# Babel_Wing_Rev_A.net
KiCad netlist of a schematic drawn in EAGLE
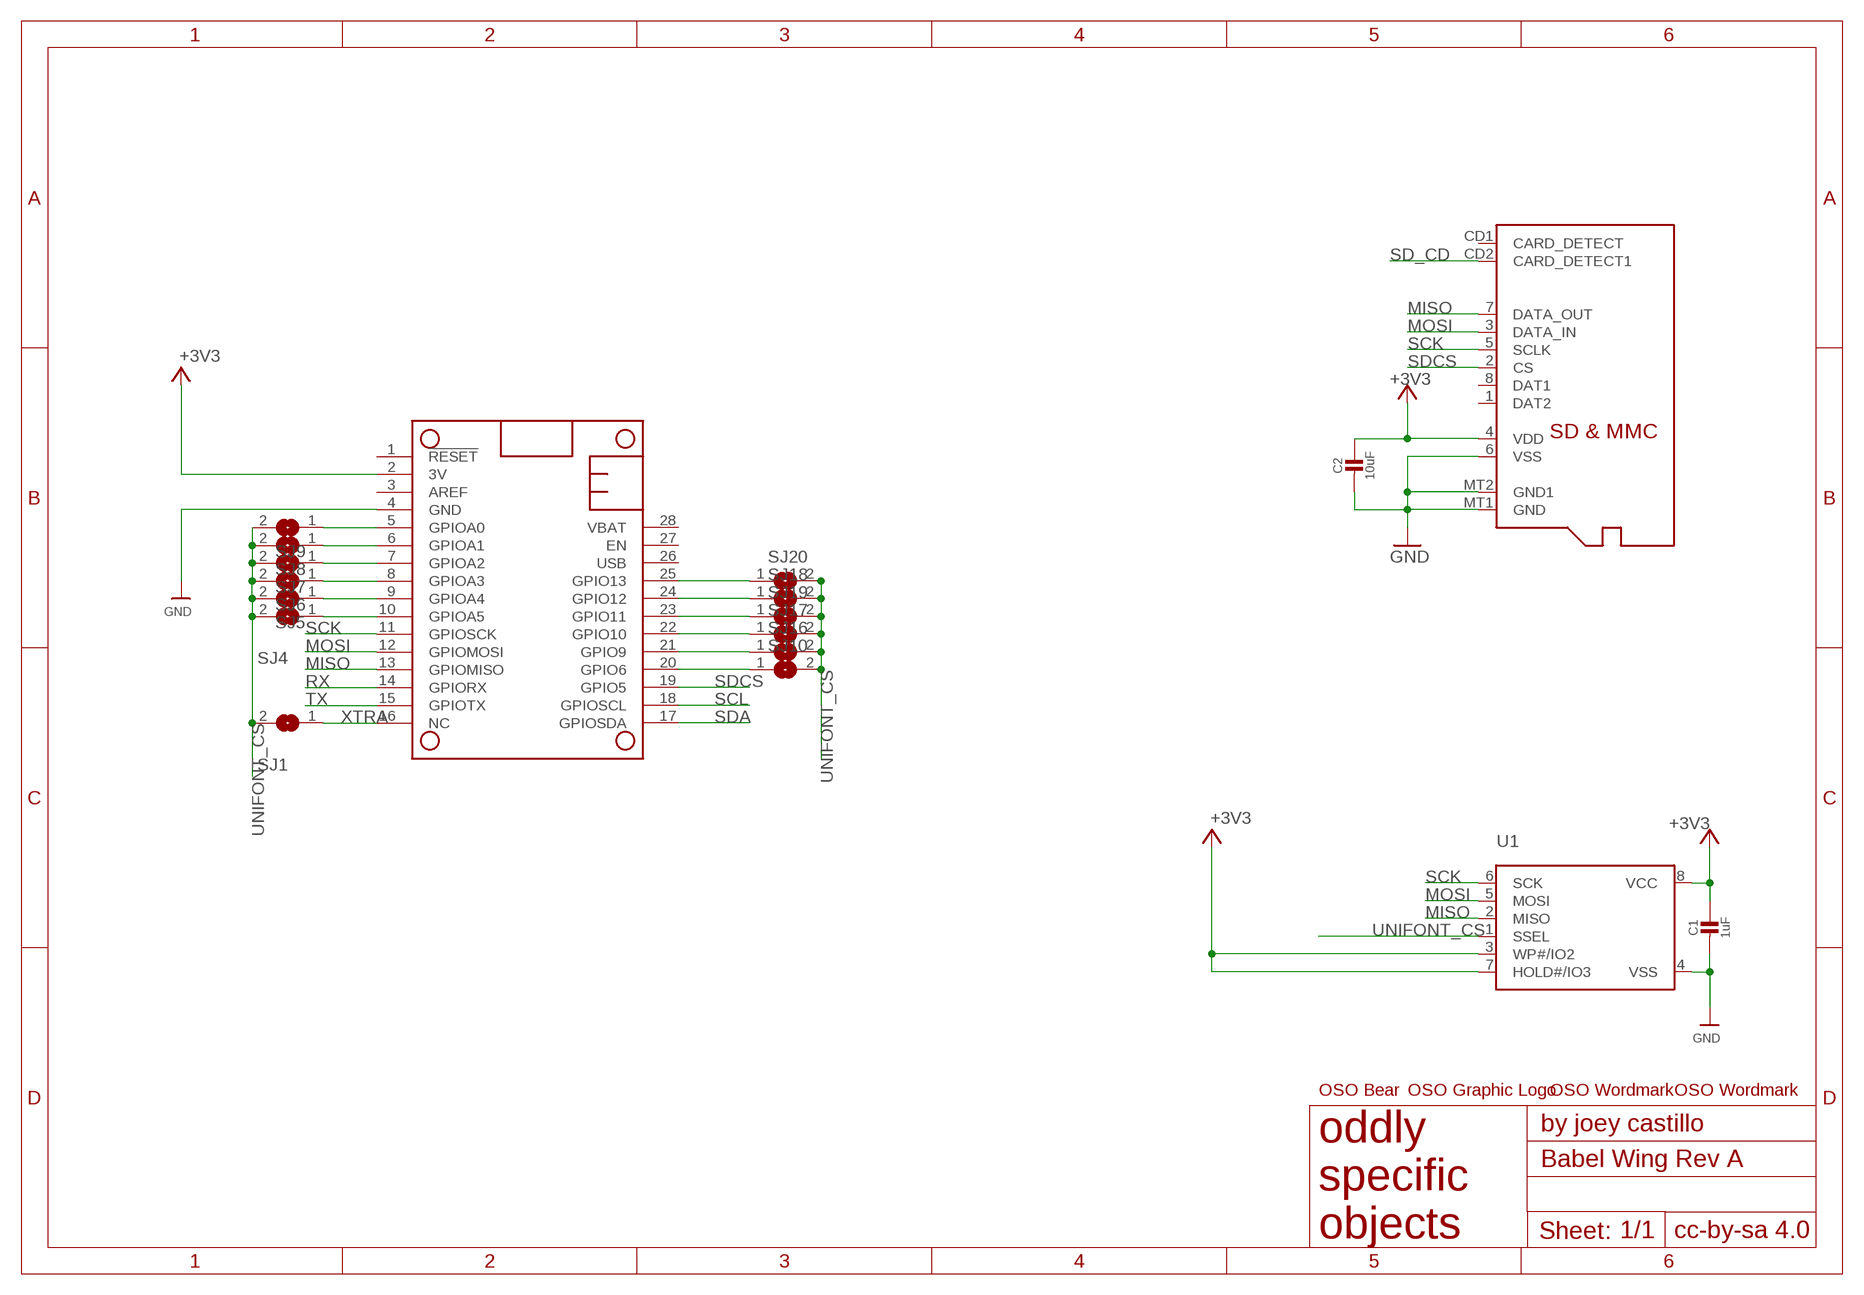
[diagram p0: schematic, sheet 1]

(export (version "E")
  (design (tool "Eeschema 10.0.6"))
  (components
    (comp (ref "C1")
      (value "1uF")
      (footprint "eagle-import:0805_10MGAP")
      (libsource (lib "eagle-import") (part "CAP_CERAMIC0805_10MGAP"))
    )
    (comp (ref "C2")
      (value "10uF")
      (footprint "eagle-import:0805_10MGAP")
      (libsource (lib "eagle-import") (part "CAP_CERAMIC0805_10MGAP"))
    )
    (comp (ref "MICROSD")
      (value "MICROSD")
      (footprint "eagle-import:MICROSD")
      (libsource (lib "eagle-import") (part "MICROSD"))
    )
    (comp (ref "MS1")
      (value "FEATHERWING")
      (footprint "eagle-import:FEATHERWING")
      (libsource (lib "eagle-import") (part "FEATHERWING"))
    )
    (comp (ref "SJ1")
      (value "SOLDERJUMPER")
      (footprint "eagle-import:SOLDERJUMPER_ARROW_NOPASTE")
      (libsource (lib "eagle-import") (part "SOLDERJUMPER"))
    )
    (comp (ref "SJ4")
      (value "SOLDERJUMPER")
      (footprint "eagle-import:SOLDERJUMPER_ARROW_NOPASTE")
      (libsource (lib "eagle-import") (part "SOLDERJUMPER"))
    )
    (comp (ref "SJ5")
      (value "SOLDERJUMPER")
      (footprint "eagle-import:SOLDERJUMPER_ARROW_NOPASTE")
      (libsource (lib "eagle-import") (part "SOLDERJUMPER"))
    )
    (comp (ref "SJ6")
      (value "SOLDERJUMPER")
      (footprint "eagle-import:SOLDERJUMPER_ARROW_NOPASTE")
      (libsource (lib "eagle-import") (part "SOLDERJUMPER"))
    )
    (comp (ref "SJ7")
      (value "SOLDERJUMPER")
      (footprint "eagle-import:SOLDERJUMPER_ARROW_NOPASTE")
      (libsource (lib "eagle-import") (part "SOLDERJUMPER"))
    )
    (comp (ref "SJ8")
      (value "SOLDERJUMPER")
      (footprint "eagle-import:SOLDERJUMPER_ARROW_NOPASTE")
      (libsource (lib "eagle-import") (part "SOLDERJUMPER"))
    )
    (comp (ref "SJ9")
      (value "SOLDERJUMPER")
      (footprint "eagle-import:SOLDERJUMPER_ARROW_NOPASTE")
      (libsource (lib "eagle-import") (part "SOLDERJUMPER"))
    )
    (comp (ref "SJ10")
      (value "SOLDERJUMPER")
      (footprint "eagle-import:SOLDERJUMPER_ARROW_NOPASTE")
      (libsource (lib "eagle-import") (part "SOLDERJUMPER"))
    )
    (comp (ref "SJ16")
      (value "SOLDERJUMPER")
      (footprint "eagle-import:SOLDERJUMPER_ARROW_NOPASTE")
      (libsource (lib "eagle-import") (part "SOLDERJUMPER"))
    )
    (comp (ref "SJ17")
      (value "SOLDERJUMPER")
      (footprint "eagle-import:SOLDERJUMPER_ARROW_NOPASTE")
      (libsource (lib "eagle-import") (part "SOLDERJUMPER"))
    )
    (comp (ref "SJ18")
      (value "SOLDERJUMPER")
      (footprint "eagle-import:SOLDERJUMPER_ARROW_NOPASTE")
      (libsource (lib "eagle-import") (part "SOLDERJUMPER"))
    )
    (comp (ref "SJ19")
      (value "SOLDERJUMPER")
      (footprint "eagle-import:SOLDERJUMPER_ARROW_NOPASTE")
      (libsource (lib "eagle-import") (part "SOLDERJUMPER"))
    )
    (comp (ref "SJ20")
      (value "SOLDERJUMPER")
      (footprint "eagle-import:SOLDERJUMPER_ARROW_NOPASTE")
      (libsource (lib "eagle-import") (part "SOLDERJUMPER"))
    )
    (comp (ref "U$2")
      (value "OSO_BEAR")
      (footprint "eagle-import:OSO_BEAR_750MIL")
      (libsource (lib "eagle-import") (part "OSO_BEAR"))
    )
    (comp (ref "U$3")
      (value "OSO_GRAPHIC")
      (footprint "eagle-import:OSO_GRAPHIC")
      (libsource (lib "eagle-import") (part "OSO_GRAPHIC"))
    )
    (comp (ref "U$4")
      (value "OSO_TEXT")
      (footprint "eagle-import:OSO_TEXT_435MIL")
      (libsource (lib "eagle-import") (part "OSO_TEXT"))
    )
    (comp (ref "U$5")
      (value "OSO_TEXTOSO_TEXT_ONELINE_125MIL")
      (footprint "eagle-import:OSO_ONELINE_125MIL")
      (libsource (lib "eagle-import") (part "OSO_TEXTOSO_TEXT_ONELINE_125MIL"))
    )
    (comp (ref "U1")
      (value "MICROBUILDER_SPIFLASH_SOIC8")
      (footprint "eagle-import:MICROBUILDER_SOIC8_150MIL")
      (libsource (lib "eagle-import") (part "MICROBUILDER_SPIFLASH_SOIC8"))
    )
  )
  (nets
    (net (code "1") (name "+3V3") (class "Default")
      (node (ref "C1") (pin "1") (pinfunction "1_1") (pintype "passive"))
      (node (ref "C2") (pin "1") (pinfunction "1_1") (pintype "passive"))
      (node (ref "MICROSD") (pin "4") (pinfunction "VDD_4") (pintype "power_in"))
      (node (ref "MS1") (pin "2") (pinfunction "3V_2") (pintype "power_in"))
      (node (ref "U1") (pin "3") (pinfunction "WP#/IO2_3") (pintype "bidirectional"))
      (node (ref "U1") (pin "7") (pinfunction "HOLD#/IO3_7") (pintype "bidirectional"))
      (node (ref "U1") (pin "8") (pinfunction "VCC_8") (pintype "bidirectional"))
    )
    (net (code "2") (name "/MISO") (class "Default")
      (node (ref "MICROSD") (pin "7") (pinfunction "DATA_OUT_7") (pintype "output"))
      (node (ref "MS1") (pin "13") (pinfunction "GPIOMISO_13") (pintype "bidirectional"))
      (node (ref "U1") (pin "2") (pinfunction "MISO_2") (pintype "bidirectional"))
    )
    (net (code "3") (name "/MOSI") (class "Default")
      (node (ref "MICROSD") (pin "3") (pinfunction "DATA_IN_3") (pintype "input"))
      (node (ref "MS1") (pin "12") (pinfunction "GPIOMOSI_12") (pintype "bidirectional"))
      (node (ref "U1") (pin "5") (pinfunction "MOSI_5") (pintype "bidirectional"))
    )
    (net (code "4") (name "/RX") (class "Default")
      (node (ref "MS1") (pin "14") (pinfunction "GPIORX_14") (pintype "bidirectional"))
    )
    (net (code "5") (name "/SCK") (class "Default")
      (node (ref "MICROSD") (pin "5") (pinfunction "SCLK_5") (pintype "input"))
      (node (ref "MS1") (pin "11") (pinfunction "GPIOSCK_11") (pintype "bidirectional"))
      (node (ref "U1") (pin "6") (pinfunction "SCK_6") (pintype "bidirectional"))
    )
    (net (code "6") (name "/SCL") (class "Default")
      (node (ref "MS1") (pin "18") (pinfunction "GPIOSCL_18") (pintype "bidirectional"))
    )
    (net (code "7") (name "/SDA") (class "Default")
      (node (ref "MS1") (pin "17") (pinfunction "GPIOSDA_17") (pintype "bidirectional"))
    )
    (net (code "8") (name "/SDCS") (class "Default")
      (node (ref "MICROSD") (pin "2") (pinfunction "CS_2") (pintype "input"))
      (node (ref "MS1") (pin "19") (pinfunction "GPIO5_19") (pintype "bidirectional"))
    )
    (net (code "9") (name "/SD_CD") (class "Default")
      (node (ref "MICROSD") (pin "CD2") (pinfunction "CARD_DETECT1_CD2") (pintype "passive"))
    )
    (net (code "10") (name "/TX") (class "Default")
      (node (ref "MS1") (pin "15") (pinfunction "GPIOTX_15") (pintype "bidirectional"))
    )
    (net (code "11") (name "/UNIFONT_CS") (class "Default")
      (node (ref "SJ1") (pin "2") (pinfunction "2_2") (pintype "passive"))
      (node (ref "SJ10") (pin "2") (pinfunction "2_2") (pintype "passive"))
      (node (ref "SJ16") (pin "2") (pinfunction "2_2") (pintype "passive"))
      (node (ref "SJ17") (pin "2") (pinfunction "2_2") (pintype "passive"))
      (node (ref "SJ18") (pin "2") (pinfunction "2_2") (pintype "passive"))
      (node (ref "SJ19") (pin "2") (pinfunction "2_2") (pintype "passive"))
      (node (ref "SJ20") (pin "2") (pinfunction "2_2") (pintype "passive"))
      (node (ref "SJ4") (pin "2") (pinfunction "2_2") (pintype "passive"))
      (node (ref "SJ5") (pin "2") (pinfunction "2_2") (pintype "passive"))
      (node (ref "SJ6") (pin "2") (pinfunction "2_2") (pintype "passive"))
      (node (ref "SJ7") (pin "2") (pinfunction "2_2") (pintype "passive"))
      (node (ref "SJ8") (pin "2") (pinfunction "2_2") (pintype "passive"))
      (node (ref "SJ9") (pin "2") (pinfunction "2_2") (pintype "passive"))
      (node (ref "U1") (pin "1") (pinfunction "SSEL_1") (pintype "bidirectional"))
    )
    (net (code "12") (name "/USB") (class "Default")
      (node (ref "MS1") (pin "26") (pinfunction "USB_26") (pintype "power_in"))
    )
    (net (code "13") (name "/VBAT") (class "Default")
      (node (ref "MS1") (pin "28") (pinfunction "VBAT_28") (pintype "power_in"))
    )
    (net (code "14") (name "/XTRA") (class "Default")
      (node (ref "MS1") (pin "16") (pinfunction "NC_16") (pintype "passive"))
      (node (ref "SJ1") (pin "1") (pinfunction "1_1") (pintype "passive"))
    )
    (net (code "15") (name "GND") (class "Default")
      (node (ref "C1") (pin "2") (pinfunction "2_2") (pintype "passive"))
      (node (ref "C2") (pin "2") (pinfunction "2_2") (pintype "passive"))
      (node (ref "MICROSD") (pin "6") (pinfunction "VSS_6") (pintype "power_in"))
      (node (ref "MICROSD") (pin "MT1") (pinfunction "GND_MT1") (pintype "power_in"))
      (node (ref "MICROSD") (pin "MT2") (pinfunction "GND1_MT2") (pintype "power_in"))
      (node (ref "MS1") (pin "4") (pinfunction "GND_4") (pintype "power_in"))
      (node (ref "U1") (pin "4") (pinfunction "VSS_4") (pintype "bidirectional"))
    )
    (net (code "16") (name "Net-(MS1-GPIO6)") (class "Default")
      (node (ref "MS1") (pin "20") (pinfunction "GPIO6_20") (pintype "bidirectional"))
      (node (ref "SJ10") (pin "1") (pinfunction "1_1") (pintype "passive"))
    )
    (net (code "17") (name "Net-(MS1-GPIO9)") (class "Default")
      (node (ref "MS1") (pin "21") (pinfunction "GPIO9_21") (pintype "bidirectional"))
      (node (ref "SJ16") (pin "1") (pinfunction "1_1") (pintype "passive"))
    )
    (net (code "18") (name "Net-(MS1-GPIO10)") (class "Default")
      (node (ref "MS1") (pin "22") (pinfunction "GPIO10_22") (pintype "bidirectional"))
      (node (ref "SJ17") (pin "1") (pinfunction "1_1") (pintype "passive"))
    )
    (net (code "19") (name "Net-(MS1-GPIO11)") (class "Default")
      (node (ref "MS1") (pin "23") (pinfunction "GPIO11_23") (pintype "bidirectional"))
      (node (ref "SJ19") (pin "1") (pinfunction "1_1") (pintype "passive"))
    )
    (net (code "20") (name "Net-(MS1-GPIO12)") (class "Default")
      (node (ref "MS1") (pin "24") (pinfunction "GPIO12_24") (pintype "bidirectional"))
      (node (ref "SJ18") (pin "1") (pinfunction "1_1") (pintype "passive"))
    )
    (net (code "21") (name "Net-(MS1-GPIO13)") (class "Default")
      (node (ref "MS1") (pin "25") (pinfunction "GPIO13_25") (pintype "bidirectional"))
      (node (ref "SJ20") (pin "1") (pinfunction "1_1") (pintype "passive"))
    )
    (net (code "22") (name "Net-(MS1-GPIOA0)") (class "Default")
      (node (ref "MS1") (pin "5") (pinfunction "GPIOA0_5") (pintype "bidirectional"))
      (node (ref "SJ9") (pin "1") (pinfunction "1_1") (pintype "passive"))
    )
    (net (code "23") (name "Net-(MS1-GPIOA1)") (class "Default")
      (node (ref "MS1") (pin "6") (pinfunction "GPIOA1_6") (pintype "bidirectional"))
      (node (ref "SJ8") (pin "1") (pinfunction "1_1") (pintype "passive"))
    )
    (net (code "24") (name "Net-(MS1-GPIOA2)") (class "Default")
      (node (ref "MS1") (pin "7") (pinfunction "GPIOA2_7") (pintype "bidirectional"))
      (node (ref "SJ7") (pin "1") (pinfunction "1_1") (pintype "passive"))
    )
    (net (code "25") (name "Net-(MS1-GPIOA3)") (class "Default")
      (node (ref "MS1") (pin "8") (pinfunction "GPIOA3_8") (pintype "bidirectional"))
      (node (ref "SJ6") (pin "1") (pinfunction "1_1") (pintype "passive"))
    )
    (net (code "26") (name "Net-(MS1-GPIOA4)") (class "Default")
      (node (ref "MS1") (pin "9") (pinfunction "GPIOA4_9") (pintype "bidirectional"))
      (node (ref "SJ5") (pin "1") (pinfunction "1_1") (pintype "passive"))
    )
    (net (code "27") (name "Net-(MS1-GPIOA5)") (class "Default")
      (node (ref "MS1") (pin "10") (pinfunction "GPIOA5_10") (pintype "bidirectional"))
      (node (ref "SJ4") (pin "1") (pinfunction "1_1") (pintype "passive"))
    )
    (net (code "28") (name "unconnected-(MICROSD-CARD_DETECT-PadCD1)") (class "Default")
      (node (ref "MICROSD") (pin "CD1") (pinfunction "CARD_DETECT_CD1") (pintype "passive"))
    )
    (net (code "29") (name "unconnected-(MICROSD-DAT1-Pad8)") (class "Default")
      (node (ref "MICROSD") (pin "8") (pinfunction "DAT1_8") (pintype "bidirectional"))
    )
    (net (code "30") (name "unconnected-(MICROSD-DAT2-Pad1)") (class "Default")
      (node (ref "MICROSD") (pin "1") (pinfunction "DAT2_1") (pintype "bidirectional"))
    )
    (net (code "31") (name "unconnected-(MS1-AREF-Pad3)") (class "Default")
      (node (ref "MS1") (pin "3") (pinfunction "AREF_3") (pintype "passive"))
    )
    (net (code "32") (name "unconnected-(MS1-EN-Pad27)") (class "Default")
      (node (ref "MS1") (pin "27") (pinfunction "EN_27") (pintype "passive"))
    )
    (net (code "33") (name "unconnected-(MS1-~{RESET}-Pad1)") (class "Default")
      (node (ref "MS1") (pin "1") (pinfunction "~{RESET}_1") (pintype "input"))
    )
  )
)
